# easyeda_schematic.net
KiCad netlist of a schematic drawn in EasyEDA
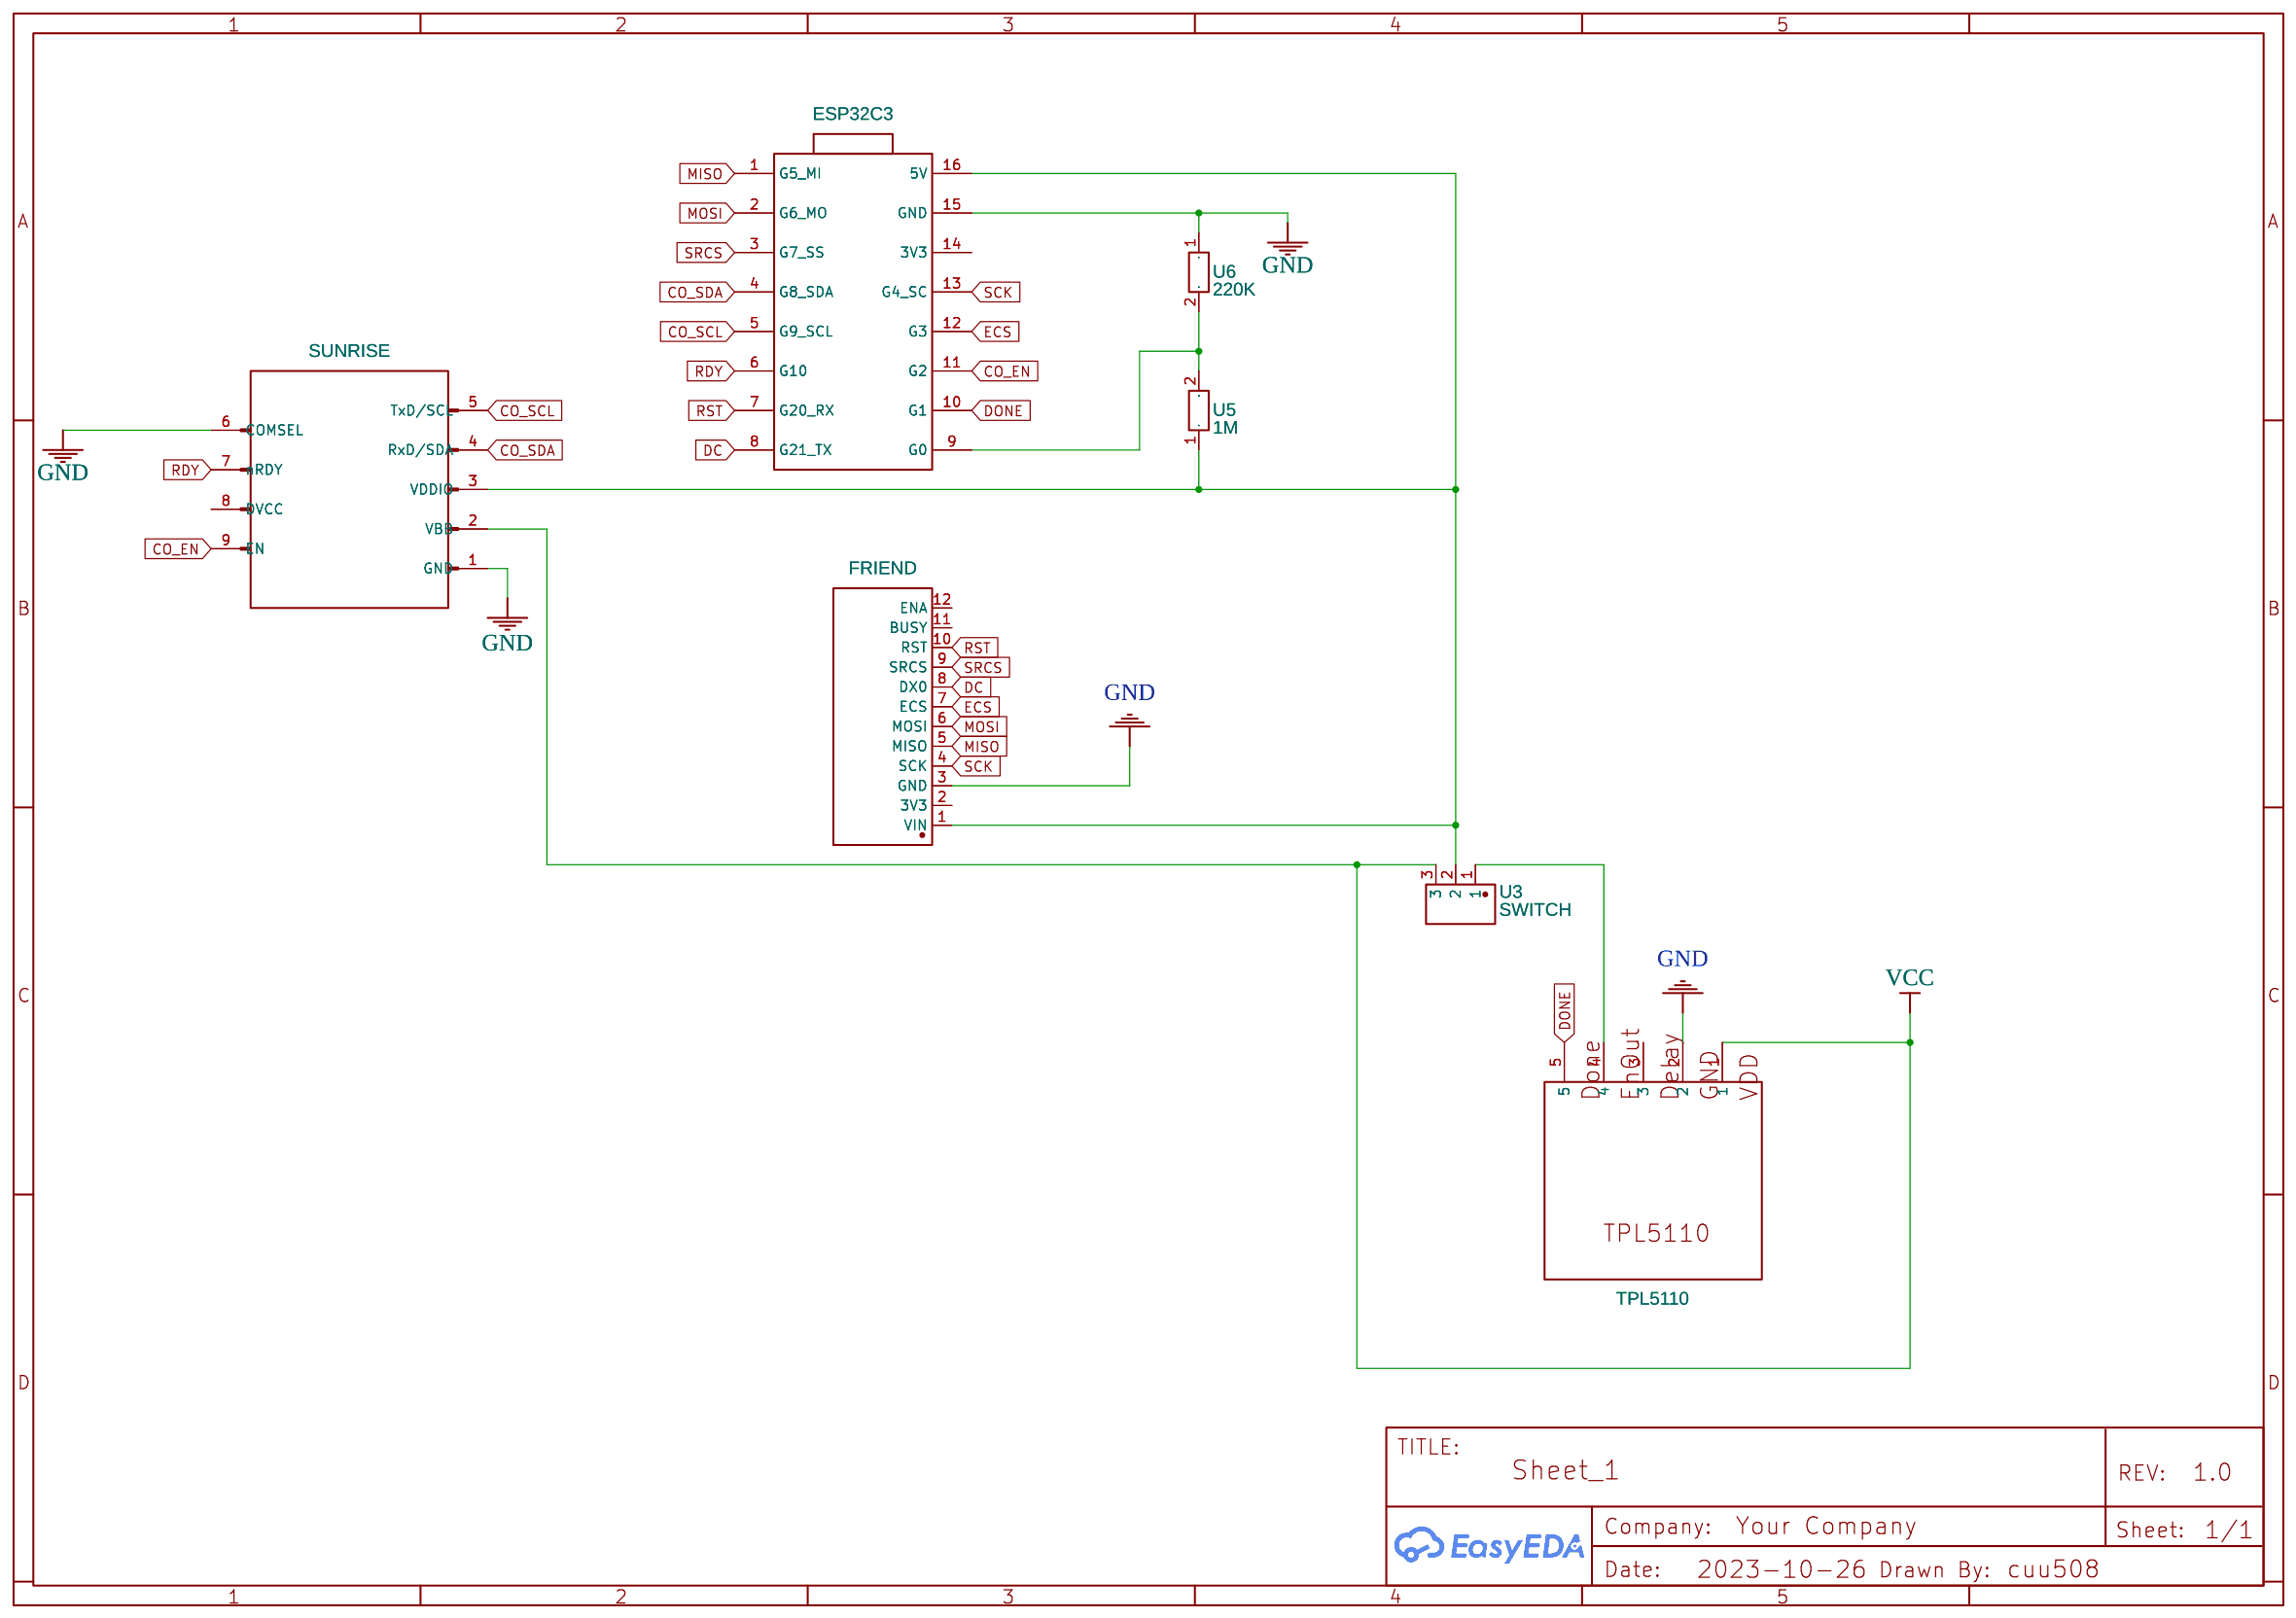
[diagram p0: schematic sheet]

(export (version "E")
  (design (tool "Eeschema 10.0.6"))
  (components
    (comp (ref "ESP32C3") (value "ESP32C3_SUPERMINI") (libsource (lib "") (part "ESP32C3_SUPERMINI")))
    (comp (ref "FRIEND")
      (value "Adafruit eInk Breakout Friend")
      (fields (field (name "Manufacturer") "Adafruit"))
      (libsource (lib "") (part "Adafruit eInk Breakout Friend"))
    )
    (comp (ref "SUNRISE") (value "SenseAir_Sunrise") (libsource (lib "") (part "SenseAir_Sunrise")))
    (comp (ref "TPL5110") (value "TPL5110") (libsource (lib "") (part "TPL5110")))
    (comp (ref "U3")
      (value "SWITCH")
      (fields (field (name "Manufacturer Part") "Jumper3"))
      (libsource (lib "") (part "JUMPER3"))
    )
    (comp (ref "U5") (value "1M") (libsource (lib "") (part "Generic Resistor_1")))
    (comp (ref "U6") (value "220K") (libsource (lib "") (part "Generic Resistor")))
  )
  (nets
    (net (code "1") (name "CO_EN") (class "Default")
      (node (ref "ESP32C3") (pin "11") (pinfunction "G2_11") (pintype "unspecified"))
      (node (ref "SUNRISE") (pin "9") (pinfunction "EN_9") (pintype "unspecified"))
    )
    (net (code "2") (name "CO_SCL") (class "Default")
      (node (ref "ESP32C3") (pin "5") (pinfunction "G9_SCL_5") (pintype "unspecified"))
      (node (ref "SUNRISE") (pin "5") (pinfunction "TxD/SCL_5") (pintype "unspecified"))
    )
    (net (code "3") (name "CO_SDA") (class "Default")
      (node (ref "ESP32C3") (pin "4") (pinfunction "G8_SDA_4") (pintype "unspecified"))
      (node (ref "SUNRISE") (pin "4") (pinfunction "RxD/SDA_4") (pintype "unspecified"))
    )
    (net (code "4") (name "DC") (class "Default")
      (node (ref "ESP32C3") (pin "8") (pinfunction "G21_TX_8") (pintype "unspecified"))
      (node (ref "FRIEND") (pin "8") (pinfunction "DX0_8") (pintype "unspecified"))
    )
    (net (code "5") (name "DONE") (class "Default")
      (node (ref "ESP32C3") (pin "10") (pinfunction "G1_10") (pintype "unspecified"))
      (node (ref "TPL5110") (pin "5") (pinfunction "5_5") (pintype "unspecified"))
    )
    (net (code "6") (name "ECS") (class "Default")
      (node (ref "ESP32C3") (pin "12") (pinfunction "G3_12") (pintype "unspecified"))
      (node (ref "FRIEND") (pin "7") (pinfunction "ECS_7") (pintype "unspecified"))
    )
    (net (code "7") (name "GND") (class "Default")
      (node (ref "ESP32C3") (pin "15") (pinfunction "GND_15") (pintype "unspecified"))
      (node (ref "FRIEND") (pin "3") (pinfunction "GND_3") (pintype "unspecified"))
      (node (ref "SUNRISE") (pin "1") (pinfunction "GND_1") (pintype "unspecified"))
      (node (ref "SUNRISE") (pin "6") (pinfunction "COMSEL_6") (pintype "unspecified"))
      (node (ref "TPL5110") (pin "2") (pinfunction "2_2") (pintype "unspecified"))
      (node (ref "U6") (pin "1") (pinfunction "1_1") (pintype "unspecified"))
    )
    (net (code "8") (name "MISO") (class "Default")
      (node (ref "ESP32C3") (pin "1") (pinfunction "G5_MI_1") (pintype "unspecified"))
      (node (ref "FRIEND") (pin "5") (pinfunction "MISO_5") (pintype "unspecified"))
    )
    (net (code "9") (name "MOSI") (class "Default")
      (node (ref "ESP32C3") (pin "2") (pinfunction "G6_MO_2") (pintype "unspecified"))
      (node (ref "FRIEND") (pin "6") (pinfunction "MOSI_6") (pintype "unspecified"))
    )
    (net (code "10") (name "Net-(ESP32C3-5V)") (class "Default")
      (node (ref "ESP32C3") (pin "16") (pinfunction "5V_16") (pintype "unspecified"))
      (node (ref "FRIEND") (pin "1") (pinfunction "VIN_1") (pintype "unspecified"))
      (node (ref "SUNRISE") (pin "3") (pinfunction "VDDIO_3") (pintype "unspecified"))
      (node (ref "U3") (pin "2") (pinfunction "2_2") (pintype "unspecified"))
      (node (ref "U5") (pin "1") (pinfunction "1_1") (pintype "unspecified"))
    )
    (net (code "11") (name "Net-(ESP32C3-G0)") (class "Default")
      (node (ref "ESP32C3") (pin "9") (pinfunction "G0_9") (pintype "unspecified"))
      (node (ref "U5") (pin "2") (pinfunction "2_2") (pintype "unspecified"))
      (node (ref "U6") (pin "2") (pinfunction "2_2") (pintype "unspecified"))
    )
    (net (code "12") (name "Net-(TPL5110-Pad4)") (class "Default")
      (node (ref "TPL5110") (pin "4") (pinfunction "4_4") (pintype "unspecified"))
      (node (ref "U3") (pin "1") (pinfunction "1_1") (pintype "unspecified"))
    )
    (net (code "13") (name "RDY") (class "Default")
      (node (ref "ESP32C3") (pin "6") (pinfunction "G10_6") (pintype "unspecified"))
      (node (ref "SUNRISE") (pin "7") (pinfunction "nRDY_7") (pintype "unspecified"))
    )
    (net (code "14") (name "RST") (class "Default")
      (node (ref "ESP32C3") (pin "7") (pinfunction "G20_RX_7") (pintype "unspecified"))
      (node (ref "FRIEND") (pin "10") (pinfunction "RST_10") (pintype "unspecified"))
    )
    (net (code "15") (name "SCK") (class "Default")
      (node (ref "ESP32C3") (pin "13") (pinfunction "G4_SC_13") (pintype "unspecified"))
      (node (ref "FRIEND") (pin "4") (pinfunction "SCK_4") (pintype "unspecified"))
    )
    (net (code "16") (name "SRCS") (class "Default")
      (node (ref "ESP32C3") (pin "3") (pinfunction "G7_SS_3") (pintype "unspecified"))
      (node (ref "FRIEND") (pin "9") (pinfunction "SRCS_9") (pintype "unspecified"))
    )
    (net (code "17") (name "VCC") (class "Default")
      (node (ref "SUNRISE") (pin "2") (pinfunction "VBB_2") (pintype "unspecified"))
      (node (ref "TPL5110") (pin "1") (pinfunction "1_1") (pintype "unspecified"))
      (node (ref "U3") (pin "3") (pinfunction "3_3") (pintype "unspecified"))
    )
    (net (code "18") (name "unconnected-(ESP32C3-3V3-Pad14)") (class "Default")
      (node (ref "ESP32C3") (pin "14") (pinfunction "3V3_14") (pintype "unspecified"))
    )
    (net (code "19") (name "unconnected-(FRIEND-3V3-Pad2)") (class "Default")
      (node (ref "FRIEND") (pin "2") (pinfunction "3V3_2") (pintype "unspecified"))
    )
    (net (code "20") (name "unconnected-(FRIEND-BUSY-Pad11)") (class "Default")
      (node (ref "FRIEND") (pin "11") (pinfunction "BUSY_11") (pintype "unspecified"))
    )
    (net (code "21") (name "unconnected-(FRIEND-ENA-Pad12)") (class "Default")
      (node (ref "FRIEND") (pin "12") (pinfunction "ENA_12") (pintype "unspecified"))
    )
    (net (code "22") (name "unconnected-(SUNRISE-DVCC-Pad8)") (class "Default")
      (node (ref "SUNRISE") (pin "8") (pinfunction "DVCC_8") (pintype "unspecified"))
    )
    (net (code "23") (name "unconnected-(TPL5110-Pad3)") (class "Default")
      (node (ref "TPL5110") (pin "3") (pinfunction "3_3") (pintype "unspecified"))
    )
  )
)
